# Emon.net
KiCad netlist of a schematic drawn in EAGLE
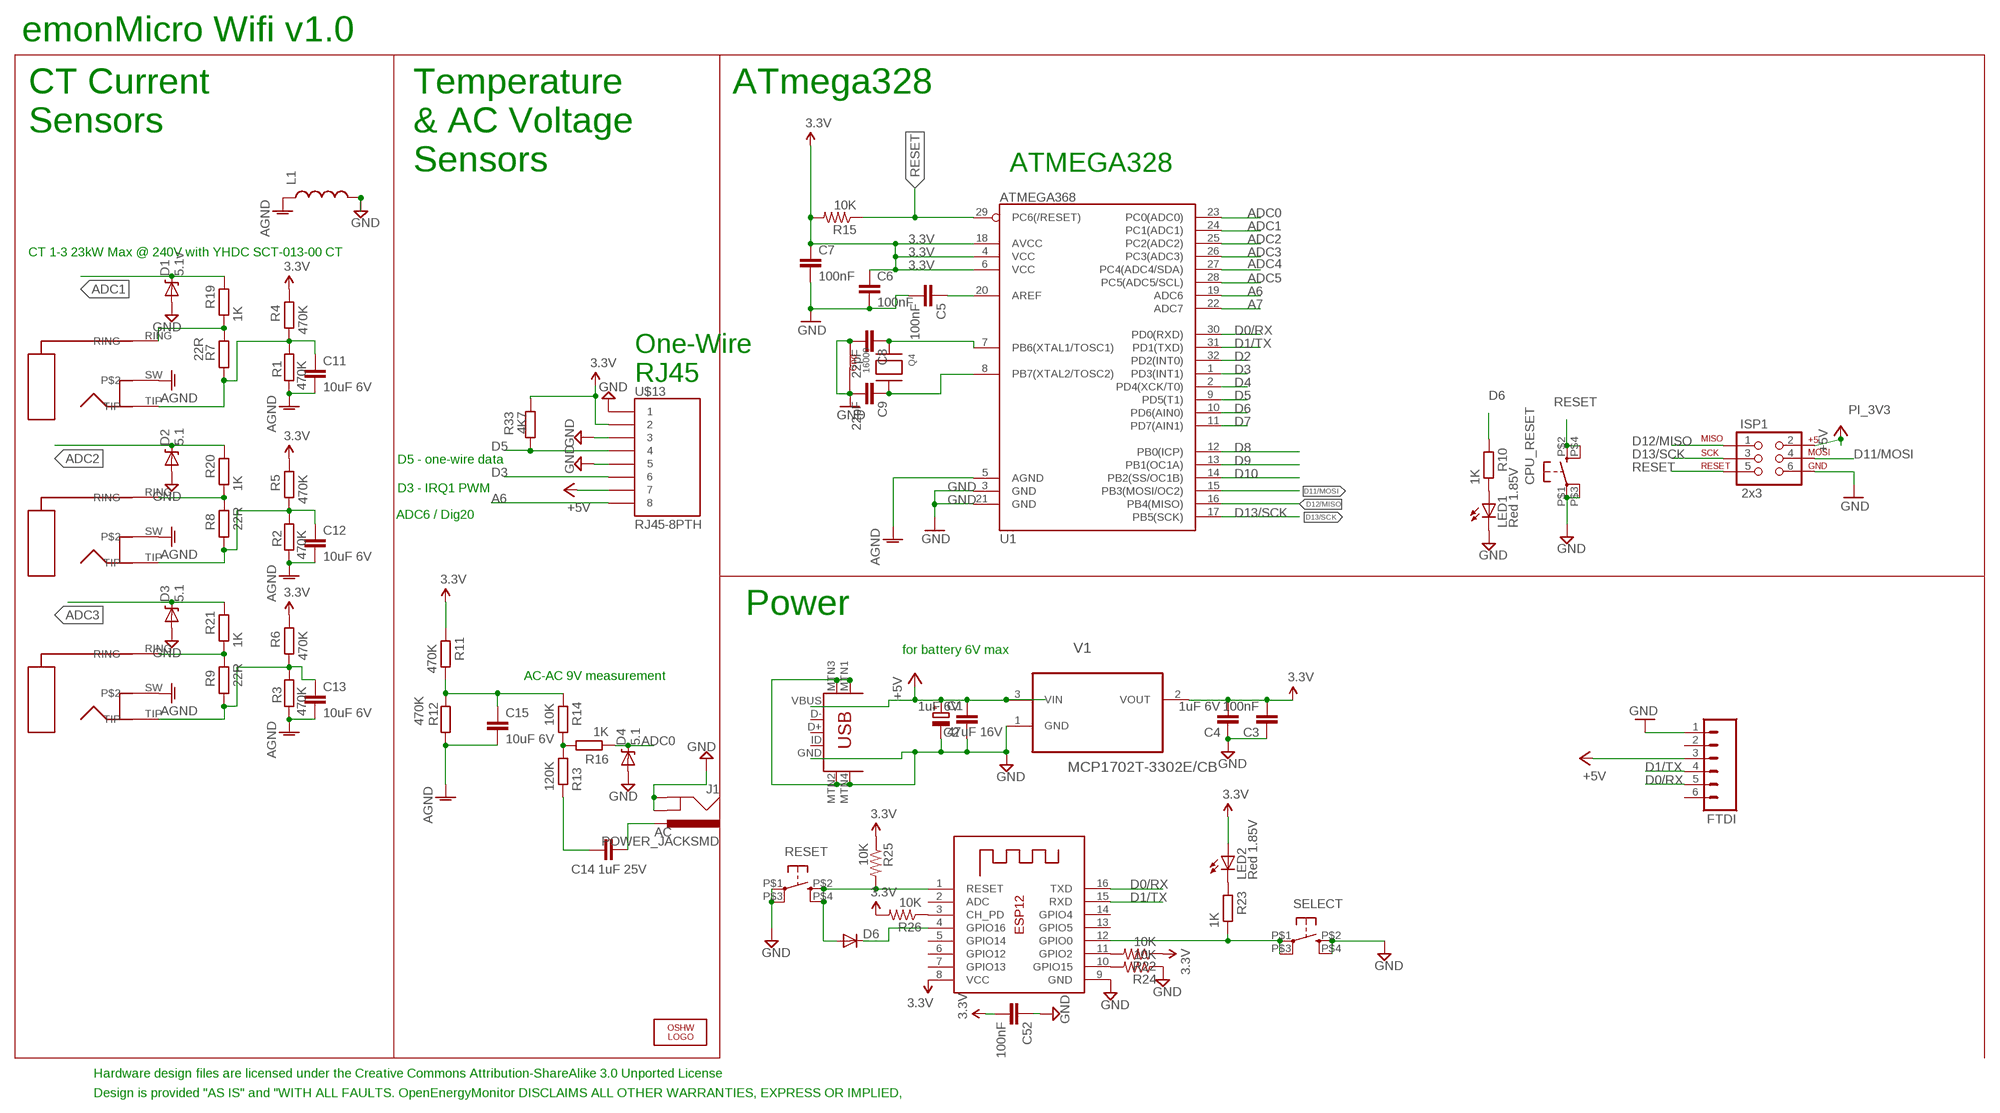
[diagram p0: schematic, sheet 1]

(export (version "E")
  (design (tool "Eeschema 10.0.6"))
  (components
    (comp (ref "C1")
      (value "47uF 16V")
      (footprint "eagle-import:PANASONIC_D")
      (libsource (lib "eagle-import") (part "CPOL-EUD"))
    )
    (comp (ref "C2")
      (value "1uF 6V")
      (footprint "eagle-import:C0603")
      (libsource (lib "eagle-import") (part "resistor_C-EUC0603"))
    )
    (comp (ref "C3")
      (value "100nF")
      (footprint "eagle-import:C0603")
      (libsource (lib "eagle-import") (part "resistor_C-EUC0603"))
    )
    (comp (ref "C4")
      (value "1uF 6V")
      (footprint "eagle-import:C0603")
      (libsource (lib "eagle-import") (part "resistor_C-EUC0603"))
    )
    (comp (ref "C5")
      (value "100nF")
      (footprint "eagle-import:C0603")
      (libsource (lib "eagle-import") (part "resistor_C-EUC0603"))
    )
    (comp (ref "C6")
      (value "100nF")
      (footprint "eagle-import:C0603")
      (libsource (lib "eagle-import") (part "resistor_C-EUC0603"))
    )
    (comp (ref "C7")
      (value "100nF")
      (footprint "eagle-import:C0603")
      (libsource (lib "eagle-import") (part "C-EUC0603"))
    )
    (comp (ref "C8")
      (value "22pF")
      (footprint "eagle-import:C0603")
      (libsource (lib "eagle-import") (part "resistor_C-EUC0603"))
    )
    (comp (ref "C9")
      (value "22pF")
      (footprint "eagle-import:C0603")
      (libsource (lib "eagle-import") (part "resistor_C-EUC0603"))
    )
    (comp (ref "C11")
      (value "10uF 6V")
      (footprint "eagle-import:C0603")
      (libsource (lib "eagle-import") (part "resistor_C-EUC0603"))
    )
    (comp (ref "C12")
      (value "10uF 6V")
      (footprint "eagle-import:C0603")
      (libsource (lib "eagle-import") (part "resistor_C-EUC0603"))
    )
    (comp (ref "C13")
      (value "10uF 6V")
      (footprint "eagle-import:C0603")
      (libsource (lib "eagle-import") (part "resistor_C-EUC0603"))
    )
    (comp (ref "C14")
      (value "1uF 25V")
      (footprint "eagle-import:C0603")
      (libsource (lib "eagle-import") (part "resistor_C-EUC0603"))
    )
    (comp (ref "C15")
      (value "10uF 6V")
      (footprint "eagle-import:C0603")
      (libsource (lib "eagle-import") (part "resistor_C-EUC0603"))
    )
    (comp (ref "C52")
      (value "100nF")
      (footprint "eagle-import:C0603")
      (libsource (lib "eagle-import") (part "resistor_C-EUC0603"))
    )
    (comp (ref "CPU_RESET")
      (value "KMR211GLFS")
      (footprint "eagle-import:PUSHBUTTON-KMR241GLFS")
      (libsource (lib "eagle-import") (part "BUTTON-KMR241GLFS"))
    )
    (comp (ref "D1")
      (value "5.1v")
      (footprint "eagle-import:SOD-323")
      (libsource (lib "eagle-import") (part "DIODE-ZENER-BZT52"))
    )
    (comp (ref "D2")
      (value "5.1")
      (footprint "eagle-import:SOD-323")
      (libsource (lib "eagle-import") (part "DIODE-ZENER-BZT52"))
    )
    (comp (ref "D3")
      (value "5.1")
      (footprint "eagle-import:SOD-323")
      (libsource (lib "eagle-import") (part "DIODE-ZENER-BZT52"))
    )
    (comp (ref "D4")
      (value "5.1")
      (footprint "eagle-import:SOD-323")
      (libsource (lib "eagle-import") (part "DIODE-ZENER-BZT52"))
    )
    (comp (ref "D6")
      (value "DIODESOD")
      (footprint "eagle-import:SOD-323")
      (libsource (lib "eagle-import") (part "DIODESOD"))
    )
    (comp (ref "FTDI")
      (value "M06LOCK")
      (footprint "eagle-import:1X06_LOCK")
      (libsource (lib "eagle-import") (part "M06LOCK"))
    )
    (comp (ref "ISP1")
      (value "2x3")
      (footprint "eagle-import:2X3")
      (libsource (lib "eagle-import") (part "AVR_SPI_PRG_6PTH"))
    )
    (comp (ref "J1")
      (value "POWER_JACKSMD")
      (footprint "eagle-import:POWER_JACK_SMD")
      (libsource (lib "eagle-import") (part "POWER_JACKSMD"))
    )
    (comp (ref "L1")
      (value "INDUCTOR0603")
      (footprint "eagle-import:0603")
      (libsource (lib "eagle-import") (part "INDUCTOR0603"))
    )
    (comp (ref "LED1")
      (value "Red 1.85V")
      (footprint "eagle-import:CHIP-LED0805")
      (libsource (lib "eagle-import") (part "LEDCHIP-LED0805"))
    )
    (comp (ref "LED2")
      (value "Red 1.85V")
      (footprint "eagle-import:CHIP-LED0805")
      (libsource (lib "eagle-import") (part "LEDCHIP-LED0805"))
    )
    (comp (ref "LOGO1")
      (value "OSHW_LOGO_6MILX0200-NT")
      (footprint "eagle-import:OSHW_6X200_NOTEXT")
      (libsource (lib "eagle-import") (part "OSHW_LOGO_6MILX0200-NT"))
    )
    (comp (ref "Q4")
      (value "16000")
      (footprint "eagle-import:NX3225")
      (libsource (lib "eagle-import") (part "XTAL-4-3225"))
    )
    (comp (ref "R1")
      (value "470K")
      (footprint "eagle-import:R0603")
      (libsource (lib "eagle-import") (part "R-EU_R0603"))
    )
    (comp (ref "R2")
      (value "470K")
      (footprint "eagle-import:R0603")
      (libsource (lib "eagle-import") (part "R-EU_R0603"))
    )
    (comp (ref "R3")
      (value "470K")
      (footprint "eagle-import:R0603")
      (libsource (lib "eagle-import") (part "R-EU_R0603"))
    )
    (comp (ref "R4")
      (value "470K")
      (footprint "eagle-import:R0603")
      (libsource (lib "eagle-import") (part "R-EU_R0603"))
    )
    (comp (ref "R5")
      (value "470K")
      (footprint "eagle-import:R0603")
      (libsource (lib "eagle-import") (part "R-EU_R0603"))
    )
    (comp (ref "R6")
      (value "470K")
      (footprint "eagle-import:R0603")
      (libsource (lib "eagle-import") (part "R-EU_R0603"))
    )
    (comp (ref "R7")
      (value "22R")
      (footprint "eagle-import:R1206")
      (libsource (lib "eagle-import") (part "R-EU_R1206"))
    )
    (comp (ref "R8")
      (value "22R")
      (footprint "eagle-import:R1206")
      (libsource (lib "eagle-import") (part "R-EU_R1206"))
    )
    (comp (ref "R9")
      (value "22R")
      (footprint "eagle-import:R1206")
      (libsource (lib "eagle-import") (part "R-EU_R1206"))
    )
    (comp (ref "R10")
      (value "1K")
      (footprint "eagle-import:R0603")
      (libsource (lib "eagle-import") (part "R-EU_R0603"))
    )
    (comp (ref "R11")
      (value "470K")
      (footprint "eagle-import:R0603")
      (libsource (lib "eagle-import") (part "R-EU_R0603"))
    )
    (comp (ref "R12")
      (value "470K")
      (footprint "eagle-import:R0603")
      (libsource (lib "eagle-import") (part "R-EU_R0603"))
    )
    (comp (ref "R13")
      (value "120K")
      (footprint "eagle-import:R0603")
      (libsource (lib "eagle-import") (part "R-EU_R0603"))
    )
    (comp (ref "R14")
      (value "10K")
      (footprint "eagle-import:R0603")
      (libsource (lib "eagle-import") (part "R-EU_R0603"))
    )
    (comp (ref "R15")
      (value "10K")
      (footprint "eagle-import:R0603")
      (libsource (lib "eagle-import") (part "R-US_R0603"))
    )
    (comp (ref "R16")
      (value "1K")
      (footprint "eagle-import:R0603")
      (libsource (lib "eagle-import") (part "R-EU_R0603"))
    )
    (comp (ref "R19")
      (value "1K")
      (footprint "eagle-import:R0603")
      (libsource (lib "eagle-import") (part "R-EU_R0603"))
    )
    (comp (ref "R20")
      (value "1K")
      (footprint "eagle-import:R0603")
      (libsource (lib "eagle-import") (part "R-EU_R0603"))
    )
    (comp (ref "R21")
      (value "1K")
      (footprint "eagle-import:R0603")
      (libsource (lib "eagle-import") (part "R-EU_R0603"))
    )
    (comp (ref "R22")
      (value "10K")
      (footprint "eagle-import:R0603")
      (libsource (lib "eagle-import") (part "R-US_R0603"))
    )
    (comp (ref "R23")
      (value "1K")
      (footprint "eagle-import:R0603")
      (libsource (lib "eagle-import") (part "R-EU_R0603"))
    )
    (comp (ref "R24")
      (value "10K")
      (footprint "eagle-import:R0603")
      (libsource (lib "eagle-import") (part "R-US_R0603"))
    )
    (comp (ref "R25")
      (value "10K")
      (footprint "eagle-import:R0603")
      (libsource (lib "eagle-import") (part "R-US_R0603"))
    )
    (comp (ref "R26")
      (value "10K")
      (footprint "eagle-import:R0603")
      (libsource (lib "eagle-import") (part "R-US_R0603"))
    )
    (comp (ref "R33")
      (value "4K7")
      (footprint "eagle-import:R0603")
      (libsource (lib "eagle-import") (part "R-EU_R0603"))
    )
    (comp (ref "RESET")
      (value "KMR211GLFS")
      (footprint "eagle-import:PUSHBUTTON-KMR241GLFS")
      (libsource (lib "eagle-import") (part "BUTTON-KMR241GLFS"))
    )
    (comp (ref "SELECT")
      (value "KMR211GLFS")
      (footprint "eagle-import:PUSHBUTTON-KMR241GLFS")
      (libsource (lib "eagle-import") (part "BUTTON-KMR241GLFS"))
    )
    (comp (ref "U$1")
      (value "MJ-3523-SMT")
      (footprint "eagle-import:AUDIO_SMT")
      (libsource (lib "eagle-import") (part "MJ-3523-SMT"))
    )
    (comp (ref "U$2")
      (value "MJ-3523-SMT")
      (footprint "eagle-import:AUDIO_SMT")
      (libsource (lib "eagle-import") (part "MJ-3523-SMT"))
    )
    (comp (ref "U$3")
      (value "MJ-3523-SMT")
      (footprint "eagle-import:AUDIO_SMT")
      (libsource (lib "eagle-import") (part "MJ-3523-SMT"))
    )
    (comp (ref "U$13")
      (value "RJ45-8PTH")
      (footprint "eagle-import:RJ45-8")
      (libsource (lib "eagle-import") (part "RJ45-8PTH"))
    )
    (comp (ref "U1")
      (value "ATMEGA368")
      (footprint "eagle-import:TQFP32-08")
      (libsource (lib "eagle-import") (part "ATMEGA168"))
    )
    (comp (ref "USB_POWER")
      (value "USB-MINIB-5PIN")
      (footprint "eagle-import:USB-MINIB-CISECO")
      (libsource (lib "eagle-import") (part "USB-MINIB-5PIN"))
    )
    (comp (ref "V1")
      (value "MCP1702T-3302E/CB")
      (footprint "eagle-import:SOT95P237X112-3N")
      (fields (field (name "MPN") "MCP1700T-3302E/TT"))
      (libsource (lib "eagle-import") (part "MCP1700T-3302E/TT"))
    )
    (comp (ref "X1")
      (value "ESP-12")
      (footprint "eagle-import:ESP-12")
      (libsource (lib "eagle-import") (part "ESP-12"))
    )
  )
  (nets
    (net (code "1") (name "+5V") (class "Default")
      (node (ref "C1") (pin "+") (pinfunction "+_+") (pintype "passive"))
      (node (ref "C2") (pin "2") (pinfunction "2_2") (pintype "passive"))
      (node (ref "FTDI") (pin "3") (pinfunction "3_3") (pintype "passive"))
      (node (ref "ISP1") (pin "2") (pinfunction "2_2") (pintype "passive"))
      (node (ref "U$13") (pin "7") (pinfunction "7_7") (pintype "bidirectional"))
      (node (ref "USB_POWER") (pin "VBUS") (pinfunction "VBUS_VBUS") (pintype "bidirectional"))
      (node (ref "V1") (pin "3") (pinfunction "VIN_3") (pintype "input"))
    )
    (net (code "2") (name "/A6") (class "Default")
      (node (ref "U$13") (pin "8") (pinfunction "8_8") (pintype "bidirectional"))
      (node (ref "U1") (pin "19") (pinfunction "ADC6_19") (pintype "bidirectional"))
    )
    (net (code "3") (name "/A7") (class "Default")
      (node (ref "U1") (pin "22") (pinfunction "ADC7_22") (pintype "bidirectional"))
    )
    (net (code "4") (name "/AC") (class "Default")
      (node (ref "C14") (pin "2") (pinfunction "2_2") (pintype "passive"))
      (node (ref "J1") (pin "VIN0") (pinfunction "PWR_VIN0") (pintype "bidirectional"))
    )
    (net (code "5") (name "/ADC0") (class "Default")
      (node (ref "D4") (pin "1") (pinfunction "C_1") (pintype "passive"))
      (node (ref "R16") (pin "1") (pinfunction "1_1") (pintype "passive"))
      (node (ref "U1") (pin "23") (pinfunction "PC0(ADC0)_23") (pintype "bidirectional"))
    )
    (net (code "6") (name "/ADC4") (class "Default")
      (node (ref "U1") (pin "27") (pinfunction "PC4(ADC4/SDA)_27") (pintype "bidirectional"))
    )
    (net (code "7") (name "/ADC5") (class "Default")
      (node (ref "U1") (pin "28") (pinfunction "PC5(ADC5/SCL)_28") (pintype "bidirectional"))
    )
    (net (code "8") (name "/D0{slash}RX") (class "Default")
      (node (ref "FTDI") (pin "5") (pinfunction "5_5") (pintype "passive"))
      (node (ref "U1") (pin "30") (pinfunction "PD0(RXD)_30") (pintype "bidirectional"))
      (node (ref "X1") (pin "16") (pinfunction "TXD_16") (pintype "output"))
    )
    (net (code "9") (name "/D1{slash}TX") (class "Default")
      (node (ref "FTDI") (pin "4") (pinfunction "4_4") (pintype "passive"))
      (node (ref "U1") (pin "31") (pinfunction "PD1(TXD)_31") (pintype "bidirectional"))
      (node (ref "X1") (pin "15") (pinfunction "RXD_15") (pintype "input"))
    )
    (net (code "10") (name "/D2") (class "Default")
      (node (ref "U1") (pin "32") (pinfunction "PD2(INT0)_32") (pintype "bidirectional"))
    )
    (net (code "11") (name "/D3") (class "Default")
      (node (ref "U$13") (pin "6") (pinfunction "6_6") (pintype "bidirectional"))
      (node (ref "U1") (pin "1") (pinfunction "PD3(INT1)_1") (pintype "bidirectional"))
    )
    (net (code "12") (name "/D4") (class "Default")
      (node (ref "U1") (pin "2") (pinfunction "PD4(XCK/T0)_2") (pintype "bidirectional"))
    )
    (net (code "13") (name "/D5") (class "Default")
      (node (ref "R33") (pin "2") (pinfunction "2_2") (pintype "passive"))
      (node (ref "U$13") (pin "4") (pinfunction "4_4") (pintype "bidirectional"))
      (node (ref "U1") (pin "9") (pinfunction "PD5(T1)_9") (pintype "bidirectional"))
    )
    (net (code "14") (name "/D6") (class "Default")
      (node (ref "R10") (pin "2") (pinfunction "2_2") (pintype "passive"))
      (node (ref "U1") (pin "10") (pinfunction "PD6(AIN0)_10") (pintype "bidirectional"))
    )
    (net (code "15") (name "/D7") (class "Default")
      (node (ref "U1") (pin "11") (pinfunction "PD7(AIN1)_11") (pintype "bidirectional"))
    )
    (net (code "16") (name "/D8") (class "Default")
      (node (ref "U1") (pin "12") (pinfunction "PB0(ICP)_12") (pintype "bidirectional"))
    )
    (net (code "17") (name "/D9") (class "Default")
      (node (ref "U1") (pin "13") (pinfunction "PB1(OC1A)_13") (pintype "bidirectional"))
    )
    (net (code "18") (name "/D10") (class "Default")
      (node (ref "U1") (pin "14") (pinfunction "PB2(SS/OC1B)_14") (pintype "bidirectional"))
    )
    (net (code "20") (name "3.3V") (class "Default")
      (node (ref "C3") (pin "2") (pinfunction "2_2") (pintype "passive"))
      (node (ref "C4") (pin "2") (pinfunction "2_2") (pintype "passive"))
      (node (ref "C52") (pin "2") (pinfunction "2_2") (pintype "passive"))
      (node (ref "C6") (pin "1") (pinfunction "1_1") (pintype "passive"))
      (node (ref "C7") (pin "1") (pinfunction "1_1") (pintype "passive"))
      (node (ref "LED2") (pin "A") (pinfunction "A_A") (pintype "passive"))
      (node (ref "R11") (pin "2") (pinfunction "2_2") (pintype "passive"))
      (node (ref "R15") (pin "2") (pinfunction "2_2") (pintype "passive"))
      (node (ref "R22") (pin "1") (pinfunction "1_1") (pintype "passive"))
      (node (ref "R25") (pin "1") (pinfunction "1_1") (pintype "passive"))
      (node (ref "R26") (pin "2") (pinfunction "2_2") (pintype "passive"))
      (node (ref "R33") (pin "1") (pinfunction "1_1") (pintype "passive"))
      (node (ref "R4") (pin "2") (pinfunction "2_2") (pintype "passive"))
      (node (ref "R5") (pin "2") (pinfunction "2_2") (pintype "passive"))
      (node (ref "R6") (pin "2") (pinfunction "2_2") (pintype "passive"))
      (node (ref "U$13") (pin "2") (pinfunction "2_2") (pintype "bidirectional"))
      (node (ref "U1") (pin "18") (pinfunction "AVCC_18") (pintype "bidirectional"))
      (node (ref "U1") (pin "4") (pinfunction "VCC_4") (pintype "bidirectional"))
      (node (ref "U1") (pin "6") (pinfunction "VCC_6") (pintype "bidirectional"))
      (node (ref "V1") (pin "2") (pinfunction "VOUT_2") (pintype "output"))
      (node (ref "X1") (pin "8") (pinfunction "VCC_8") (pintype "power_in"))
    )
    (net (code "21") (name "ADC1") (class "Default")
      (node (ref "D1") (pin "1") (pinfunction "C_1") (pintype "passive"))
      (node (ref "R19") (pin "2") (pinfunction "2_2") (pintype "passive"))
      (node (ref "U1") (pin "24") (pinfunction "PC1(ADC1)_24") (pintype "bidirectional"))
    )
    (net (code "22") (name "ADC2") (class "Default")
      (node (ref "D2") (pin "1") (pinfunction "C_1") (pintype "passive"))
      (node (ref "R20") (pin "2") (pinfunction "2_2") (pintype "passive"))
      (node (ref "U1") (pin "25") (pinfunction "PC2(ADC2)_25") (pintype "bidirectional"))
    )
    (net (code "23") (name "ADC3") (class "Default")
      (node (ref "D3") (pin "1") (pinfunction "C_1") (pintype "passive"))
      (node (ref "R21") (pin "2") (pinfunction "2_2") (pintype "passive"))
      (node (ref "U1") (pin "26") (pinfunction "PC3(ADC3)_26") (pintype "bidirectional"))
    )
    (net (code "24") (name "AGND") (class "Default")
      (node (ref "C11") (pin "2") (pinfunction "2_2") (pintype "passive"))
      (node (ref "C12") (pin "2") (pinfunction "2_2") (pintype "passive"))
      (node (ref "C13") (pin "2") (pinfunction "2_2") (pintype "passive"))
      (node (ref "C15") (pin "2") (pinfunction "2_2") (pintype "passive"))
      (node (ref "L1") (pin "1") (pinfunction "1_1") (pintype "passive"))
      (node (ref "R1") (pin "2") (pinfunction "2_2") (pintype "passive"))
      (node (ref "R12") (pin "1") (pinfunction "1_1") (pintype "passive"))
      (node (ref "R2") (pin "2") (pinfunction "2_2") (pintype "passive"))
      (node (ref "R3") (pin "2") (pinfunction "2_2") (pintype "passive"))
      (node (ref "U$1") (pin "SW") (pinfunction "P$2_SW") (pintype "bidirectional"))
      (node (ref "U$2") (pin "SW") (pinfunction "P$2_SW") (pintype "bidirectional"))
      (node (ref "U$3") (pin "SW") (pinfunction "P$2_SW") (pintype "bidirectional"))
      (node (ref "U1") (pin "5") (pinfunction "AGND_5") (pintype "bidirectional"))
    )
    (net (code "25") (name "D11{slash}MOSI") (class "Default")
      (node (ref "ISP1") (pin "4") (pinfunction "4_4") (pintype "passive"))
      (node (ref "U1") (pin "15") (pinfunction "PB3(MOSI/OC2)_15") (pintype "bidirectional"))
    )
    (net (code "26") (name "D12{slash}MISO") (class "Default")
      (node (ref "ISP1") (pin "1") (pinfunction "1_1") (pintype "passive"))
      (node (ref "U1") (pin "16") (pinfunction "PB4(MISO)_16") (pintype "bidirectional"))
    )
    (net (code "27") (name "D13{slash}SCK") (class "Default")
      (node (ref "ISP1") (pin "3") (pinfunction "3_3") (pintype "passive"))
      (node (ref "U1") (pin "17") (pinfunction "PB5(SCK)_17") (pintype "bidirectional"))
    )
    (net (code "28") (name "GND") (class "Default")
      (node (ref "C1") (pin "-") (pinfunction "-_-") (pintype "passive"))
      (node (ref "C2") (pin "1") (pinfunction "1_1") (pintype "passive"))
      (node (ref "C3") (pin "1") (pinfunction "1_1") (pintype "passive"))
      (node (ref "C4") (pin "1") (pinfunction "1_1") (pintype "passive"))
      (node (ref "C5") (pin "2") (pinfunction "2_2") (pintype "passive"))
      (node (ref "C52") (pin "1") (pinfunction "1_1") (pintype "passive"))
      (node (ref "C6") (pin "2") (pinfunction "2_2") (pintype "passive"))
      (node (ref "C7") (pin "2") (pinfunction "2_2") (pintype "passive"))
      (node (ref "C8") (pin "2") (pinfunction "2_2") (pintype "passive"))
      (node (ref "C9") (pin "2") (pinfunction "2_2") (pintype "passive"))
      (node (ref "CPU_RESET") (pin "P$1") (pinfunction "1_P$1") (pintype "passive"))
      (node (ref "CPU_RESET") (pin "P$3") (pinfunction "3_P$3") (pintype "passive"))
      (node (ref "D1") (pin "2") (pinfunction "A_2") (pintype "passive"))
      (node (ref "D2") (pin "2") (pinfunction "A_2") (pintype "passive"))
      (node (ref "D3") (pin "2") (pinfunction "A_2") (pintype "passive"))
      (node (ref "D4") (pin "2") (pinfunction "A_2") (pintype "passive"))
      (node (ref "FTDI") (pin "1") (pinfunction "1_1") (pintype "passive"))
      (node (ref "ISP1") (pin "6") (pinfunction "6_6") (pintype "passive"))
      (node (ref "J1") (pin "GND") (pinfunction "GNDBREAK_GND") (pintype "bidirectional"))
      (node (ref "J1") (pin "P$4") (pinfunction "GND_P$4") (pintype "bidirectional"))
      (node (ref "L1") (pin "2") (pinfunction "2_2") (pintype "passive"))
      (node (ref "LED1") (pin "C") (pinfunction "C_C") (pintype "passive"))
      (node (ref "Q4") (pin "1") (pinfunction "G1_1") (pintype "power_in"))
      (node (ref "Q4") (pin "3") (pinfunction "G2_3") (pintype "power_in"))
      (node (ref "R24") (pin "1") (pinfunction "1_1") (pintype "passive"))
      (node (ref "RESET") (pin "P$1") (pinfunction "1_P$1") (pintype "passive"))
      (node (ref "RESET") (pin "P$3") (pinfunction "3_P$3") (pintype "passive"))
      (node (ref "SELECT") (pin "P$2") (pinfunction "2_P$2") (pintype "passive"))
      (node (ref "SELECT") (pin "P$4") (pinfunction "4_P$4") (pintype "passive"))
      (node (ref "U$13") (pin "1") (pinfunction "1_1") (pintype "bidirectional"))
      (node (ref "U$13") (pin "3") (pinfunction "3_3") (pintype "bidirectional"))
      (node (ref "U$13") (pin "5") (pinfunction "5_5") (pintype "bidirectional"))
      (node (ref "U1") (pin "21") (pinfunction "GND_21") (pintype "bidirectional"))
      (node (ref "U1") (pin "3") (pinfunction "GND_3") (pintype "bidirectional"))
      (node (ref "USB_POWER") (pin "GND") (pinfunction "GND_GND") (pintype "bidirectional"))
      (node (ref "USB_POWER") (pin "MTN1") (pinfunction "MTN2_MTN1") (pintype "bidirectional"))
      (node (ref "USB_POWER") (pin "MTN2") (pinfunction "MTN3_MTN2") (pintype "bidirectional"))
      (node (ref "USB_POWER") (pin "MTN3") (pinfunction "MTN1_MTN3") (pintype "bidirectional"))
      (node (ref "USB_POWER") (pin "MTN4") (pinfunction "MTN4_MTN4") (pintype "bidirectional"))
      (node (ref "V1") (pin "1") (pinfunction "GND_1") (pintype "passive"))
      (node (ref "X1") (pin "9") (pinfunction "GND_9") (pintype "power_in"))
    )
    (net (code "29") (name "Net-(C11-Pad1)") (class "Default")
      (node (ref "C11") (pin "1") (pinfunction "1_1") (pintype "passive"))
      (node (ref "R1") (pin "1") (pinfunction "1_1") (pintype "passive"))
      (node (ref "R4") (pin "1") (pinfunction "1_1") (pintype "passive"))
      (node (ref "R7") (pin "1") (pinfunction "1_1") (pintype "passive"))
      (node (ref "U$2") (pin "TIP") (pinfunction "TIP_TIP") (pintype "bidirectional"))
    )
    (net (code "30") (name "Net-(C12-Pad1)") (class "Default")
      (node (ref "C12") (pin "1") (pinfunction "1_1") (pintype "passive"))
      (node (ref "R2") (pin "1") (pinfunction "1_1") (pintype "passive"))
      (node (ref "R5") (pin "1") (pinfunction "1_1") (pintype "passive"))
      (node (ref "R8") (pin "1") (pinfunction "1_1") (pintype "passive"))
      (node (ref "U$1") (pin "TIP") (pinfunction "TIP_TIP") (pintype "bidirectional"))
    )
    (net (code "31") (name "Net-(C13-Pad1)") (class "Default")
      (node (ref "C13") (pin "1") (pinfunction "1_1") (pintype "passive"))
      (node (ref "R3") (pin "1") (pinfunction "1_1") (pintype "passive"))
      (node (ref "R6") (pin "1") (pinfunction "1_1") (pintype "passive"))
      (node (ref "R9") (pin "1") (pinfunction "1_1") (pintype "passive"))
      (node (ref "U$3") (pin "TIP") (pinfunction "TIP_TIP") (pintype "bidirectional"))
    )
    (net (code "32") (name "Net-(C14-Pad1)") (class "Default")
      (node (ref "C14") (pin "1") (pinfunction "1_1") (pintype "passive"))
      (node (ref "R13") (pin "1") (pinfunction "1_1") (pintype "passive"))
    )
    (net (code "33") (name "Net-(C15-Pad1)") (class "Default")
      (node (ref "C15") (pin "1") (pinfunction "1_1") (pintype "passive"))
      (node (ref "R11") (pin "1") (pinfunction "1_1") (pintype "passive"))
      (node (ref "R12") (pin "2") (pinfunction "2_2") (pintype "passive"))
      (node (ref "R14") (pin "2") (pinfunction "2_2") (pintype "passive"))
    )
    (net (code "34") (name "Net-(D6-A)") (class "Default")
      (node (ref "D6") (pin "2") (pinfunction "A_2") (pintype "passive"))
      (node (ref "R25") (pin "2") (pinfunction "2_2") (pintype "passive"))
      (node (ref "RESET") (pin "P$2") (pinfunction "2_P$2") (pintype "passive"))
      (node (ref "RESET") (pin "P$4") (pinfunction "4_P$4") (pintype "passive"))
      (node (ref "X1") (pin "1") (pinfunction "RESET_1") (pintype "input"))
    )
    (net (code "35") (name "Net-(D6-C)") (class "Default")
      (node (ref "D6") (pin "1") (pinfunction "C_1") (pintype "passive"))
      (node (ref "X1") (pin "4") (pinfunction "GPIO16_4") (pintype "bidirectional"))
    )
    (net (code "36") (name "Net-(LED1-PadA)") (class "Default")
      (node (ref "LED1") (pin "A") (pinfunction "A_A") (pintype "passive"))
      (node (ref "R10") (pin "1") (pinfunction "1_1") (pintype "passive"))
    )
    (net (code "37") (name "Net-(LED2-PadC)") (class "Default")
      (node (ref "LED2") (pin "C") (pinfunction "C_C") (pintype "passive"))
      (node (ref "R23") (pin "2") (pinfunction "2_2") (pintype "passive"))
    )
    (net (code "38") (name "Net-(Q4-X1)") (class "Default")
      (node (ref "C8") (pin "1") (pinfunction "1_1") (pintype "passive"))
      (node (ref "Q4") (pin "2") (pinfunction "X1_2") (pintype "bidirectional"))
      (node (ref "U1") (pin "7") (pinfunction "PB6(XTAL1/TOSC1)_7") (pintype "bidirectional"))
    )
    (net (code "39") (name "Net-(Q4-X2)") (class "Default")
      (node (ref "C9") (pin "1") (pinfunction "1_1") (pintype "passive"))
      (node (ref "Q4") (pin "4") (pinfunction "X2_4") (pintype "bidirectional"))
      (node (ref "U1") (pin "8") (pinfunction "PB7(XTAL2/TOSC2)_8") (pintype "bidirectional"))
    )
    (net (code "40") (name "Net-(R13-Pad2)") (class "Default")
      (node (ref "R13") (pin "2") (pinfunction "2_2") (pintype "passive"))
      (node (ref "R14") (pin "1") (pinfunction "1_1") (pintype "passive"))
      (node (ref "R16") (pin "2") (pinfunction "2_2") (pintype "passive"))
    )
    (net (code "41") (name "Net-(R19-Pad1)") (class "Default")
      (node (ref "R19") (pin "1") (pinfunction "1_1") (pintype "passive"))
      (node (ref "R7") (pin "2") (pinfunction "2_2") (pintype "passive"))
      (node (ref "U$2") (pin "RING") (pinfunction "RING_RING") (pintype "bidirectional"))
    )
    (net (code "42") (name "Net-(R20-Pad1)") (class "Default")
      (node (ref "R20") (pin "1") (pinfunction "1_1") (pintype "passive"))
      (node (ref "R8") (pin "2") (pinfunction "2_2") (pintype "passive"))
      (node (ref "U$1") (pin "RING") (pinfunction "RING_RING") (pintype "bidirectional"))
    )
    (net (code "43") (name "Net-(R21-Pad1)") (class "Default")
      (node (ref "R21") (pin "1") (pinfunction "1_1") (pintype "passive"))
      (node (ref "R9") (pin "2") (pinfunction "2_2") (pintype "passive"))
      (node (ref "U$3") (pin "RING") (pinfunction "RING_RING") (pintype "bidirectional"))
    )
    (net (code "44") (name "Net-(SELECT-1)") (class "Default")
      (node (ref "R23") (pin "1") (pinfunction "1_1") (pintype "passive"))
      (node (ref "SELECT") (pin "P$1") (pinfunction "1_P$1") (pintype "passive"))
      (node (ref "SELECT") (pin "P$3") (pinfunction "3_P$3") (pintype "passive"))
      (node (ref "X1") (pin "12") (pinfunction "GPIO0_12") (pintype "bidirectional"))
    )
    (net (code "45") (name "Net-(U1-AREF)") (class "Default")
      (node (ref "C5") (pin "1") (pinfunction "1_1") (pintype "passive"))
      (node (ref "U1") (pin "20") (pinfunction "AREF_20") (pintype "bidirectional"))
    )
    (net (code "46") (name "Net-(X1-CH_PD)") (class "Default")
      (node (ref "R26") (pin "1") (pinfunction "1_1") (pintype "passive"))
      (node (ref "X1") (pin "3") (pinfunction "CH_PD_3") (pintype "input"))
    )
    (net (code "47") (name "Net-(X1-GPIO2)") (class "Default")
      (node (ref "R22") (pin "2") (pinfunction "2_2") (pintype "passive"))
      (node (ref "X1") (pin "11") (pinfunction "GPIO2_11") (pintype "bidirectional"))
    )
    (net (code "48") (name "Net-(X1-GPIO15)") (class "Default")
      (node (ref "R24") (pin "2") (pinfunction "2_2") (pintype "passive"))
      (node (ref "X1") (pin "10") (pinfunction "GPIO15_10") (pintype "bidirectional"))
    )
    (net (code "49") (name "RESET") (class "Default")
      (node (ref "CPU_RESET") (pin "P$2") (pinfunction "2_P$2") (pintype "passive"))
      (node (ref "CPU_RESET") (pin "P$4") (pinfunction "4_P$4") (pintype "passive"))
      (node (ref "ISP1") (pin "5") (pinfunction "5_5") (pintype "passive"))
      (node (ref "R15") (pin "1") (pinfunction "1_1") (pintype "passive"))
      (node (ref "U1") (pin "29") (pinfunction "PC6(/RESET)_29") (pintype "bidirectional"))
    )
    (net (code "50") (name "unconnected-(FTDI-Pad2)") (class "Default")
      (node (ref "FTDI") (pin "2") (pinfunction "2_2") (pintype "passive"))
    )
    (net (code "51") (name "unconnected-(FTDI-Pad6)") (class "Default")
      (node (ref "FTDI") (pin "6") (pinfunction "6_6") (pintype "passive"))
    )
    (net (code "52") (name "unconnected-(USB_POWER-PadD+)") (class "Default")
      (node (ref "USB_POWER") (pin "D+") (pinfunction "D+_D+") (pintype "bidirectional"))
    )
    (net (code "53") (name "unconnected-(USB_POWER-PadD-)") (class "Default")
      (node (ref "USB_POWER") (pin "D-") (pinfunction "D-_D-") (pintype "bidirectional"))
    )
    (net (code "54") (name "unconnected-(USB_POWER-PadID)") (class "Default")
      (node (ref "USB_POWER") (pin "ID") (pinfunction "ID_ID") (pintype "bidirectional"))
    )
    (net (code "55") (name "unconnected-(X1-ADC-Pad2)") (class "Default")
      (node (ref "X1") (pin "2") (pinfunction "ADC_2") (pintype "passive"))
    )
    (net (code "56") (name "unconnected-(X1-GPIO4-Pad14)") (class "Default")
      (node (ref "X1") (pin "14") (pinfunction "GPIO4_14") (pintype "bidirectional"))
    )
    (net (code "57") (name "unconnected-(X1-GPIO5-Pad13)") (class "Default")
      (node (ref "X1") (pin "13") (pinfunction "GPIO5_13") (pintype "bidirectional"))
    )
    (net (code "58") (name "unconnected-(X1-GPIO12-Pad6)") (class "Default")
      (node (ref "X1") (pin "6") (pinfunction "GPIO12_6") (pintype "bidirectional"))
    )
    (net (code "59") (name "unconnected-(X1-GPIO13-Pad7)") (class "Default")
      (node (ref "X1") (pin "7") (pinfunction "GPIO13_7") (pintype "bidirectional"))
    )
    (net (code "60") (name "unconnected-(X1-GPIO14-Pad5)") (class "Default")
      (node (ref "X1") (pin "5") (pinfunction "GPIO14_5") (pintype "bidirectional"))
    )
  )
)
